# power_unit.net
KiCad netlist of a schematic drawn in Altium Designer
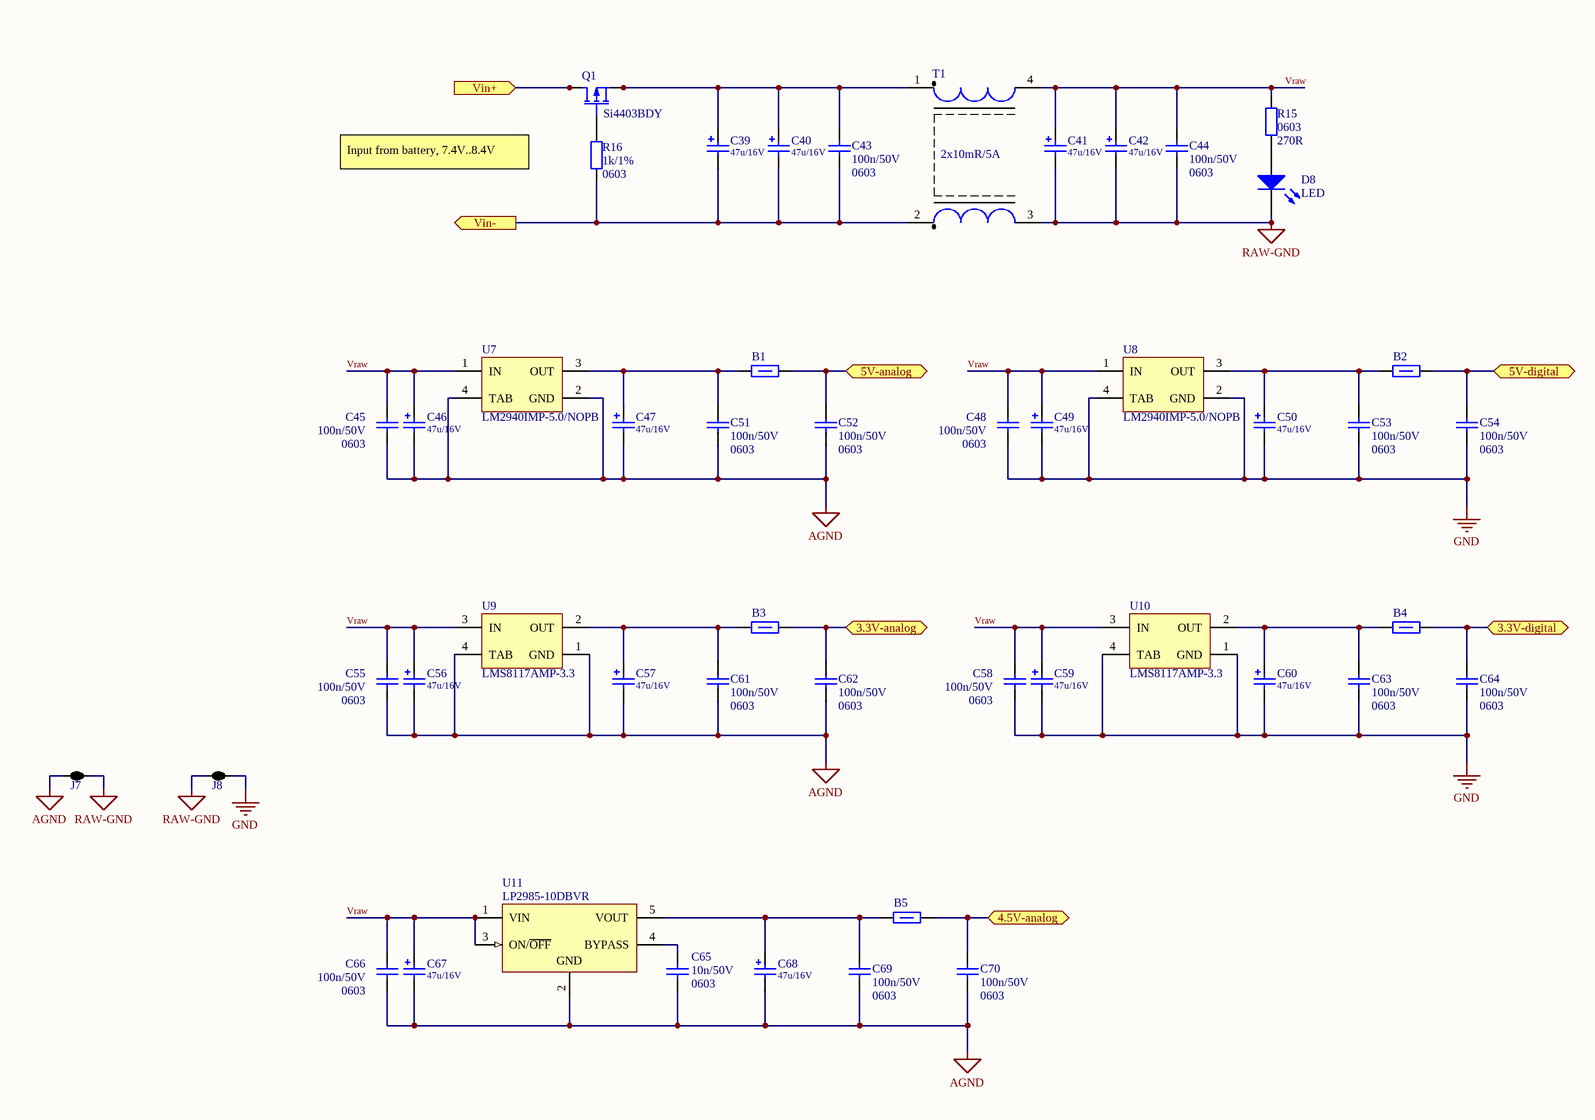
[diagram p0: power_unit.SchDoc]

(export (version "E")
  (design (tool "Eeschema 10.0.6"))
  (components
    (comp (ref "B1")
      (value "120R/100MHz")
      (footprint "SMD_FerriteBead_1206")
      (description "Ferrite bead, 1206, 0.02HM, 3.5A.")
      (fields (field (name "MANUFACTURER") "Murata") (field (name "MANUFACTURERPARTNUMBER") "BLM31PG121SH1L"))
      (libsource (lib "inductors") (part "BLM31PG121SH1L"))
    )
    (comp (ref "B2")
      (value "120R/100MHz")
      (footprint "SMD_FerriteBead_1206")
      (description "Ferrite bead, 1206, 0.02HM, 3.5A.")
      (fields (field (name "MANUFACTURER") "Murata") (field (name "MANUFACTURERPARTNUMBER") "BLM31PG121SH1L"))
      (libsource (lib "inductors") (part "BLM31PG121SH1L"))
    )
    (comp (ref "B3")
      (value "120R/100MHz")
      (footprint "SMD_FerriteBead_1206")
      (description "Ferrite bead, 1206, 0.02HM, 3.5A.")
      (fields (field (name "MANUFACTURER") "Murata") (field (name "MANUFACTURERPARTNUMBER") "BLM31PG121SH1L"))
      (libsource (lib "inductors") (part "BLM31PG121SH1L"))
    )
    (comp (ref "B4")
      (value "120R/100MHz")
      (footprint "SMD_FerriteBead_1206")
      (description "Ferrite bead, 1206, 0.02HM, 3.5A.")
      (fields (field (name "MANUFACTURER") "Murata") (field (name "MANUFACTURERPARTNUMBER") "BLM31PG121SH1L"))
      (libsource (lib "inductors") (part "BLM31PG121SH1L"))
    )
    (comp (ref "B5")
      (value "120R/100MHz")
      (footprint "SMD_FerriteBead_1206")
      (description "Ferrite bead, 1206, 0.02HM, 3.5A.")
      (fields (field (name "MANUFACTURER") "Murata") (field (name "MANUFACTURERPARTNUMBER") "BLM31PG121SH1L"))
      (libsource (lib "inductors") (part "BLM31PG121SH1L"))
    )
    (comp (ref "C39")
      (value "47u/16V")
      (footprint "Tantalum_cap_B")
      (description "Tantalum Capacitor")
      (libsource (lib "GG") (part "Cap Tantalum"))
    )
    (comp (ref "C40")
      (value "47u/16V")
      (footprint "Tantalum_cap_B")
      (description "Tantalum Capacitor")
      (libsource (lib "GG") (part "Cap Tantalum"))
    )
    (comp (ref "C41")
      (value "47u/16V")
      (footprint "Tantalum_cap_B")
      (description "Tantalum Capacitor")
      (libsource (lib "GG") (part "Cap Tantalum"))
    )
    (comp (ref "C42")
      (value "47u/16V")
      (footprint "Tantalum_cap_B")
      (description "Tantalum Capacitor")
      (libsource (lib "GG") (part "Cap Tantalum"))
    )
    (comp (ref "C43")
      (value "100n/50V")
      (footprint "SMD_Capacitor_0603")
      (description "Ceramic Cap Kemet COTS 100n/50V X7R 0603")
      (fields
        (field (name "MANUFACTURER") "Kemet")
        (field (name "MANUFACTURERPARTNUMBER") "C0603T104K5RALTU")
        (field (name "PACKAGE") "0603")
      )
      (libsource (lib "capacitors") (part "Cer_C0603T104K5RALTU"))
    )
    (comp (ref "C44")
      (value "100n/50V")
      (footprint "SMD_Capacitor_0603")
      (description "Ceramic Cap Kemet COTS 100n/50V X7R 0603")
      (fields
        (field (name "MANUFACTURER") "Kemet")
        (field (name "MANUFACTURERPARTNUMBER") "C0603T104K5RALTU")
        (field (name "PACKAGE") "0603")
      )
      (libsource (lib "capacitors") (part "Cer_C0603T104K5RALTU"))
    )
    (comp (ref "C45")
      (value "100n/50V")
      (footprint "SMD_Capacitor_0603")
      (description "Ceramic Cap Kemet COTS 100n/50V X7R 0603")
      (fields
        (field (name "MANUFACTURER") "Kemet")
        (field (name "MANUFACTURERPARTNUMBER") "C0603T104K5RALTU")
        (field (name "PACKAGE") "0603")
      )
      (libsource (lib "capacitors") (part "Cer_C0603T104K5RALTU"))
    )
    (comp (ref "C46")
      (value "47u/16V")
      (footprint "Tantalum_cap_B")
      (description "Tantalum Capacitor")
      (libsource (lib "GG") (part "Cap Tantalum"))
    )
    (comp (ref "C47")
      (value "47u/16V")
      (footprint "Tantalum_cap_B")
      (description "Tantalum Capacitor")
      (libsource (lib "GG") (part "Cap Tantalum"))
    )
    (comp (ref "C48")
      (value "100n/50V")
      (footprint "SMD_Capacitor_0603")
      (description "Ceramic Cap Kemet COTS 100n/50V X7R 0603")
      (fields
        (field (name "MANUFACTURER") "Kemet")
        (field (name "MANUFACTURERPARTNUMBER") "C0603T104K5RALTU")
        (field (name "PACKAGE") "0603")
      )
      (libsource (lib "capacitors") (part "Cer_C0603T104K5RALTU"))
    )
    (comp (ref "C49")
      (value "47u/16V")
      (footprint "Tantalum_cap_B")
      (description "Tantalum Capacitor")
      (libsource (lib "GG") (part "Cap Tantalum"))
    )
    (comp (ref "C50")
      (value "47u/16V")
      (footprint "Tantalum_cap_B")
      (description "Tantalum Capacitor")
      (libsource (lib "GG") (part "Cap Tantalum"))
    )
    (comp (ref "C51")
      (value "100n/50V")
      (footprint "SMD_Capacitor_0603")
      (description "Ceramic Cap Kemet COTS 100n/50V X7R 0603")
      (fields
        (field (name "MANUFACTURER") "Kemet")
        (field (name "MANUFACTURERPARTNUMBER") "C0603T104K5RALTU")
        (field (name "PACKAGE") "0603")
      )
      (libsource (lib "capacitors") (part "Cer_C0603T104K5RALTU"))
    )
    (comp (ref "C52")
      (value "100n/50V")
      (footprint "SMD_Capacitor_0603")
      (description "Ceramic Cap Kemet COTS 100n/50V X7R 0603")
      (fields
        (field (name "MANUFACTURER") "Kemet")
        (field (name "MANUFACTURERPARTNUMBER") "C0603T104K5RALTU")
        (field (name "PACKAGE") "0603")
      )
      (libsource (lib "capacitors") (part "Cer_C0603T104K5RALTU"))
    )
    (comp (ref "C53")
      (value "100n/50V")
      (footprint "SMD_Capacitor_0603")
      (description "Ceramic Cap Kemet COTS 100n/50V X7R 0603")
      (fields
        (field (name "MANUFACTURER") "Kemet")
        (field (name "MANUFACTURERPARTNUMBER") "C0603T104K5RALTU")
        (field (name "PACKAGE") "0603")
      )
      (libsource (lib "capacitors") (part "Cer_C0603T104K5RALTU"))
    )
    (comp (ref "C54")
      (value "100n/50V")
      (footprint "SMD_Capacitor_0603")
      (description "Ceramic Cap Kemet COTS 100n/50V X7R 0603")
      (fields
        (field (name "MANUFACTURER") "Kemet")
        (field (name "MANUFACTURERPARTNUMBER") "C0603T104K5RALTU")
        (field (name "PACKAGE") "0603")
      )
      (libsource (lib "capacitors") (part "Cer_C0603T104K5RALTU"))
    )
    (comp (ref "C55")
      (value "100n/50V")
      (footprint "SMD_Capacitor_0603")
      (description "Ceramic Cap Kemet COTS 100n/50V X7R 0603")
      (fields
        (field (name "MANUFACTURER") "Kemet")
        (field (name "MANUFACTURERPARTNUMBER") "C0603T104K5RALTU")
        (field (name "PACKAGE") "0603")
      )
      (libsource (lib "capacitors") (part "Cer_C0603T104K5RALTU"))
    )
    (comp (ref "C56")
      (value "47u/16V")
      (footprint "Tantalum_cap_B")
      (description "Tantalum Capacitor")
      (libsource (lib "GG") (part "Cap Tantalum"))
    )
    (comp (ref "C57")
      (value "47u/16V")
      (footprint "Tantalum_cap_B")
      (description "Tantalum Capacitor")
      (libsource (lib "GG") (part "Cap Tantalum"))
    )
    (comp (ref "C58")
      (value "100n/50V")
      (footprint "SMD_Capacitor_0603")
      (description "Ceramic Cap Kemet COTS 100n/50V X7R 0603")
      (fields
        (field (name "MANUFACTURER") "Kemet")
        (field (name "MANUFACTURERPARTNUMBER") "C0603T104K5RALTU")
        (field (name "PACKAGE") "0603")
      )
      (libsource (lib "capacitors") (part "Cer_C0603T104K5RALTU"))
    )
    (comp (ref "C59")
      (value "47u/16V")
      (footprint "Tantalum_cap_B")
      (description "Tantalum Capacitor")
      (libsource (lib "GG") (part "Cap Tantalum"))
    )
    (comp (ref "C60")
      (value "47u/16V")
      (footprint "Tantalum_cap_B")
      (description "Tantalum Capacitor")
      (libsource (lib "GG") (part "Cap Tantalum"))
    )
    (comp (ref "C61")
      (value "100n/50V")
      (footprint "SMD_Capacitor_0603")
      (description "Ceramic Cap Kemet COTS 100n/50V X7R 0603")
      (fields
        (field (name "MANUFACTURER") "Kemet")
        (field (name "MANUFACTURERPARTNUMBER") "C0603T104K5RALTU")
        (field (name "PACKAGE") "0603")
      )
      (libsource (lib "capacitors") (part "Cer_C0603T104K5RALTU"))
    )
    (comp (ref "C62")
      (value "100n/50V")
      (footprint "SMD_Capacitor_0603")
      (description "Ceramic Cap Kemet COTS 100n/50V X7R 0603")
      (fields
        (field (name "MANUFACTURER") "Kemet")
        (field (name "MANUFACTURERPARTNUMBER") "C0603T104K5RALTU")
        (field (name "PACKAGE") "0603")
      )
      (libsource (lib "capacitors") (part "Cer_C0603T104K5RALTU"))
    )
    (comp (ref "C63")
      (value "100n/50V")
      (footprint "SMD_Capacitor_0603")
      (description "Ceramic Cap Kemet COTS 100n/50V X7R 0603")
      (fields
        (field (name "MANUFACTURER") "Kemet")
        (field (name "MANUFACTURERPARTNUMBER") "C0603T104K5RALTU")
        (field (name "PACKAGE") "0603")
      )
      (libsource (lib "capacitors") (part "Cer_C0603T104K5RALTU"))
    )
    (comp (ref "C64")
      (value "100n/50V")
      (footprint "SMD_Capacitor_0603")
      (description "Ceramic Cap Kemet COTS 100n/50V X7R 0603")
      (fields
        (field (name "MANUFACTURER") "Kemet")
        (field (name "MANUFACTURERPARTNUMBER") "C0603T104K5RALTU")
        (field (name "PACKAGE") "0603")
      )
      (libsource (lib "capacitors") (part "Cer_C0603T104K5RALTU"))
    )
    (comp (ref "C65")
      (value "10n/50V")
      (footprint "SMD_Capacitor_0603")
      (description "Cap")
      (fields (field (name "PACKAGE") "0603"))
      (libsource (lib "capacitors") (part "Cap"))
    )
    (comp (ref "C66")
      (value "100n/50V")
      (footprint "SMD_Capacitor_0603")
      (description "Ceramic Cap Kemet COTS 100n/50V X7R 0603")
      (fields
        (field (name "MANUFACTURER") "Kemet")
        (field (name "MANUFACTURERPARTNUMBER") "C0603T104K5RALTU")
        (field (name "PACKAGE") "0603")
      )
      (libsource (lib "capacitors") (part "Cer_C0603T104K5RALTU"))
    )
    (comp (ref "C67")
      (value "47u/16V")
      (footprint "Tantalum_cap_B")
      (description "Tantalum Capacitor")
      (libsource (lib "GG") (part "Cap Tantalum"))
    )
    (comp (ref "C68")
      (value "47u/16V")
      (footprint "Tantalum_cap_B")
      (description "Tantalum Capacitor")
      (libsource (lib "GG") (part "Cap Tantalum"))
    )
    (comp (ref "C69")
      (value "100n/50V")
      (footprint "SMD_Capacitor_0603")
      (description "Ceramic Cap Kemet COTS 100n/50V X7R 0603")
      (fields
        (field (name "MANUFACTURER") "Kemet")
        (field (name "MANUFACTURERPARTNUMBER") "C0603T104K5RALTU")
        (field (name "PACKAGE") "0603")
      )
      (libsource (lib "capacitors") (part "Cer_C0603T104K5RALTU"))
    )
    (comp (ref "C70")
      (value "100n/50V")
      (footprint "SMD_Capacitor_0603")
      (description "Ceramic Cap Kemet COTS 100n/50V X7R 0603")
      (fields
        (field (name "MANUFACTURER") "Kemet")
        (field (name "MANUFACTURERPARTNUMBER") "C0603T104K5RALTU")
        (field (name "PACKAGE") "0603")
      )
      (libsource (lib "capacitors") (part "Cer_C0603T104K5RALTU"))
    )
    (comp (ref "D8")
      (value "LED")
      (footprint "LED 0805 RED")
      (description "Typical BLUE SiC LED")
      (fields (field (name "PUBLISHER") "Altium Limited"))
      (libsource (lib "Miscellaneous Devices") (part "LED3"))
    )
    (comp (ref "J7")
      (value "2 way net tie junction")
      (footprint "2way_MP")
      (libsource (lib "NetTieLib") (part "2way"))
    )
    (comp (ref "J8")
      (value "2 way net tie junction")
      (footprint "2way_MP")
      (libsource (lib "NetTieLib") (part "2way"))
    )
    (comp (ref "Q1")
      (value "Si4403BDY")
      (footprint "SOIC-8_M")
      (description "P-Channel 1.8 V (G-S) MOSFET")
      (libsource (lib "GG") (part "Si4403BDY"))
    )
    (comp (ref "R15")
      (value "0603")
      (footprint "SMD_Resistor_0603")
      (description "Resistor")
      (fields (field (name "ALTIUM_VALUE") "270R") (field (name "PUBLISHER") "Altium Limited"))
      (libsource (lib "Miscellaneous Devices") (part "Res2"))
    )
    (comp (ref "R16")
      (value "1k/1%")
      (footprint "SMD_Resistor_0603")
      (description "1k/1% Vishay CRCW 0603 Resistor. 100mW, 100ppm, 75V.")
      (fields
        (field (name "MANUFACTURER") "Vishay")
        (field (name "MANUFACTURERPARTNUMBER") "CRCW06031K00FKxxxx")
        (field (name "PACKAGE") "0603")
      )
      (libsource (lib "resistors") (part "CRCW06031K00FKxxxx"))
    )
    (comp (ref "T1")
      (value "2x10mR/5A")
      (footprint "TDK_ACM7060")
      (description "TDK ACM7060-301 Common Mode Choke")
      (fields
        (field (name "MANUFACTURER") "TDK")
        (field (name "MANUFACTURERPARTNUMBER") "ACM7060-301-2PL-TL01")
      )
      (libsource (lib "GG") (part "ACM7060-301-2PL-TL01"))
    )
    (comp (ref "U7")
      (value "LM2940IMP-5.0/NOPB")
      (footprint "MP04A_N")
      (description "1A Low Dropout Regulator, 4-pin SOT-223, Pb-Free")
      (fields (field (name "MANUFACTURER") "National Semiconductor"))
      (libsource (lib "National Semiconductor LDO") (part "LM2940IMP-5.0/NOPB"))
    )
    (comp (ref "U8")
      (value "LM2940IMP-5.0/NOPB")
      (footprint "MP04A_N")
      (description "1A Low Dropout Regulator, 4-pin SOT-223, Pb-Free")
      (fields (field (name "MANUFACTURER") "National Semiconductor"))
      (libsource (lib "National Semiconductor LDO") (part "LM2940IMP-5.0/NOPB"))
    )
    (comp (ref "U9")
      (value "LMS8117AMP-3.3")
      (footprint "MP04A_M")
      (description "1A Low-Dropout Linear Regulator, 4-pin SOT-223")
      (fields (field (name "MANUFACTURER") "National Semiconductor"))
      (libsource (lib "National Semiconductor LDO") (part "LMS8117AMP-3.3"))
    )
    (comp (ref "U10")
      (value "LMS8117AMP-3.3")
      (footprint "MP04A_M")
      (description "1A Low-Dropout Linear Regulator, 4-pin SOT-223")
      (fields (field (name "MANUFACTURER") "National Semiconductor"))
      (libsource (lib "National Semiconductor LDO") (part "LMS8117AMP-3.3"))
    )
    (comp (ref "U11")
      (value "LP2985-10DBVR")
      (footprint "TI-DBV5_N")
      (fields (field (name "MANUFACTURER") "Texas Instruments"))
      (libsource (lib "TI Power Management Linear Regulator Single Channel LDO (0-350mA)") (part "LP2985-10DBVR"))
    )
  )
  (nets
    (net (code "1") (name "/3.3V-analog") (class "Default")
      (node (ref "B3") (pin "2") (pinfunction "2_2") (pintype "passive"))
      (node (ref "C62") (pin "1") (pinfunction "1_1") (pintype "passive"))
    )
    (net (code "2") (name "/3.3V-digital") (class "Default")
      (node (ref "B4") (pin "2") (pinfunction "2_2") (pintype "passive"))
      (node (ref "C64") (pin "1") (pinfunction "1_1") (pintype "passive"))
    )
    (net (code "3") (name "/4.5V-analog") (class "Default")
      (node (ref "B5") (pin "2") (pinfunction "2_2") (pintype "passive"))
      (node (ref "C70") (pin "1") (pinfunction "1_1") (pintype "passive"))
    )
    (net (code "4") (name "/5V-analog") (class "Default")
      (node (ref "B1") (pin "2") (pinfunction "2_2") (pintype "passive"))
      (node (ref "C52") (pin "1") (pinfunction "1_1") (pintype "passive"))
    )
    (net (code "5") (name "/5V-digital") (class "Default")
      (node (ref "B2") (pin "2") (pinfunction "2_2") (pintype "passive"))
      (node (ref "C54") (pin "1") (pinfunction "1_1") (pintype "passive"))
    )
    (net (code "6") (name "/Vin+") (class "Default")
      (node (ref "Q1") (pin "5") (pinfunction "D_5") (pintype "passive"))
      (node (ref "Q1") (pin "6") (pinfunction "D_6") (pintype "passive"))
      (node (ref "Q1") (pin "7") (pinfunction "D_7") (pintype "passive"))
      (node (ref "Q1") (pin "8") (pinfunction "D_8") (pintype "passive"))
    )
    (net (code "7") (name "/Vin-") (class "Default")
      (node (ref "C39") (pin "2") (pinfunction "2_2") (pintype "passive"))
      (node (ref "C40") (pin "2") (pinfunction "2_2") (pintype "passive"))
      (node (ref "C43") (pin "2") (pinfunction "2_2") (pintype "passive"))
      (node (ref "R16") (pin "2") (pinfunction "2_2") (pintype "passive"))
      (node (ref "T1") (pin "2") (pinfunction "2_2") (pintype "passive"))
    )
    (net (code "8") (name "/Vraw") (class "Default")
      (node (ref "C41") (pin "1") (pinfunction "1_1") (pintype "passive"))
      (node (ref "C42") (pin "1") (pinfunction "1_1") (pintype "passive"))
      (node (ref "C44") (pin "1") (pinfunction "1_1") (pintype "passive"))
      (node (ref "C45") (pin "1") (pinfunction "1_1") (pintype "passive"))
      (node (ref "C46") (pin "1") (pinfunction "1_1") (pintype "passive"))
      (node (ref "C48") (pin "1") (pinfunction "1_1") (pintype "passive"))
      (node (ref "C49") (pin "1") (pinfunction "1_1") (pintype "passive"))
      (node (ref "C55") (pin "1") (pinfunction "1_1") (pintype "passive"))
      (node (ref "C56") (pin "1") (pinfunction "1_1") (pintype "passive"))
      (node (ref "C58") (pin "1") (pinfunction "1_1") (pintype "passive"))
      (node (ref "C59") (pin "1") (pinfunction "1_1") (pintype "passive"))
      (node (ref "C66") (pin "1") (pinfunction "1_1") (pintype "passive"))
      (node (ref "C67") (pin "1") (pinfunction "1_1") (pintype "passive"))
      (node (ref "R15") (pin "1") (pinfunction "1_1") (pintype "passive"))
      (node (ref "T1") (pin "4") (pinfunction "4_4") (pintype "passive"))
      (node (ref "U10") (pin "3") (pinfunction "IN_3") (pintype "power_in"))
      (node (ref "U11") (pin "1") (pinfunction "VIN_1") (pintype "power_in"))
      (node (ref "U11") (pin "3") (pinfunction "ON/~{OFF}_3") (pintype "input"))
      (node (ref "U7") (pin "1") (pinfunction "IN_1") (pintype "power_in"))
      (node (ref "U8") (pin "1") (pinfunction "IN_1") (pintype "power_in"))
      (node (ref "U9") (pin "3") (pinfunction "IN_3") (pintype "power_in"))
    )
    (net (code "9") (name "AGND") (class "Default")
      (node (ref "C45") (pin "2") (pinfunction "2_2") (pintype "passive"))
      (node (ref "C46") (pin "2") (pinfunction "2_2") (pintype "passive"))
      (node (ref "C47") (pin "2") (pinfunction "2_2") (pintype "passive"))
      (node (ref "C51") (pin "2") (pinfunction "2_2") (pintype "passive"))
      (node (ref "C52") (pin "2") (pinfunction "2_2") (pintype "passive"))
      (node (ref "C55") (pin "2") (pinfunction "2_2") (pintype "passive"))
      (node (ref "C56") (pin "2") (pinfunction "2_2") (pintype "passive"))
      (node (ref "C57") (pin "2") (pinfunction "2_2") (pintype "passive"))
      (node (ref "C61") (pin "2") (pinfunction "2_2") (pintype "passive"))
      (node (ref "C62") (pin "2") (pinfunction "2_2") (pintype "passive"))
      (node (ref "C65") (pin "2") (pinfunction "2_2") (pintype "passive"))
      (node (ref "C66") (pin "2") (pinfunction "2_2") (pintype "passive"))
      (node (ref "C67") (pin "2") (pinfunction "2_2") (pintype "passive"))
      (node (ref "C68") (pin "2") (pinfunction "2_2") (pintype "passive"))
      (node (ref "C69") (pin "2") (pinfunction "2_2") (pintype "passive"))
      (node (ref "C70") (pin "2") (pinfunction "2_2") (pintype "passive"))
      (node (ref "J7") (pin "2") (pinfunction "2_2") (pintype "passive"))
      (node (ref "U11") (pin "2") (pinfunction "GND_2") (pintype "power_in"))
      (node (ref "U7") (pin "2") (pinfunction "GND_2") (pintype "power_in"))
      (node (ref "U7") (pin "4") (pinfunction "TAB_4") (pintype "power_in"))
      (node (ref "U9") (pin "1") (pinfunction "GND_1") (pintype "power_in"))
      (node (ref "U9") (pin "4") (pinfunction "TAB_4") (pintype "power_in"))
    )
    (net (code "10") (name "GND") (class "Default")
      (node (ref "C48") (pin "2") (pinfunction "2_2") (pintype "passive"))
      (node (ref "C49") (pin "2") (pinfunction "2_2") (pintype "passive"))
      (node (ref "C50") (pin "2") (pinfunction "2_2") (pintype "passive"))
      (node (ref "C53") (pin "2") (pinfunction "2_2") (pintype "passive"))
      (node (ref "C54") (pin "2") (pinfunction "2_2") (pintype "passive"))
      (node (ref "C58") (pin "2") (pinfunction "2_2") (pintype "passive"))
      (node (ref "C59") (pin "2") (pinfunction "2_2") (pintype "passive"))
      (node (ref "C60") (pin "2") (pinfunction "2_2") (pintype "passive"))
      (node (ref "C63") (pin "2") (pinfunction "2_2") (pintype "passive"))
      (node (ref "C64") (pin "2") (pinfunction "2_2") (pintype "passive"))
      (node (ref "J8") (pin "1") (pinfunction "1_1") (pintype "passive"))
      (node (ref "U10") (pin "1") (pinfunction "GND_1") (pintype "power_in"))
      (node (ref "U10") (pin "4") (pinfunction "TAB_4") (pintype "power_in"))
      (node (ref "U8") (pin "2") (pinfunction "GND_2") (pintype "power_in"))
      (node (ref "U8") (pin "4") (pinfunction "TAB_4") (pintype "power_in"))
    )
    (net (code "11") (name "Net-(C39-Pad1)") (class "Default")
      (node (ref "C39") (pin "1") (pinfunction "1_1") (pintype "passive"))
      (node (ref "C40") (pin "1") (pinfunction "1_1") (pintype "passive"))
      (node (ref "C43") (pin "1") (pinfunction "1_1") (pintype "passive"))
      (node (ref "Q1") (pin "1") (pinfunction "S_1") (pintype "passive"))
      (node (ref "Q1") (pin "2") (pinfunction "S_2") (pintype "passive"))
      (node (ref "Q1") (pin "3") (pinfunction "S_3") (pintype "passive"))
      (node (ref "T1") (pin "1") (pinfunction "1_1") (pintype "passive"))
    )
    (net (code "12") (name "Net-(D8-A)") (class "Default")
      (node (ref "D8") (pin "1") (pinfunction "A_1") (pintype "passive"))
      (node (ref "R15") (pin "2") (pinfunction "2_2") (pintype "passive"))
    )
    (net (code "13") (name "Net-(Q1-G)") (class "Default")
      (node (ref "Q1") (pin "4") (pinfunction "G_4") (pintype "passive"))
      (node (ref "R16") (pin "1") (pinfunction "1_1") (pintype "passive"))
    )
    (net (code "14") (name "Net-(U7-OUT)") (class "Default")
      (node (ref "B1") (pin "1") (pinfunction "1_1") (pintype "passive"))
      (node (ref "C47") (pin "1") (pinfunction "1_1") (pintype "passive"))
      (node (ref "C51") (pin "1") (pinfunction "1_1") (pintype "passive"))
      (node (ref "U7") (pin "3") (pinfunction "OUT_3") (pintype "power_in"))
    )
    (net (code "15") (name "Net-(U8-OUT)") (class "Default")
      (node (ref "B2") (pin "1") (pinfunction "1_1") (pintype "passive"))
      (node (ref "C50") (pin "1") (pinfunction "1_1") (pintype "passive"))
      (node (ref "C53") (pin "1") (pinfunction "1_1") (pintype "passive"))
      (node (ref "U8") (pin "3") (pinfunction "OUT_3") (pintype "power_in"))
    )
    (net (code "16") (name "Net-(U9-OUT)") (class "Default")
      (node (ref "B3") (pin "1") (pinfunction "1_1") (pintype "passive"))
      (node (ref "C57") (pin "1") (pinfunction "1_1") (pintype "passive"))
      (node (ref "C61") (pin "1") (pinfunction "1_1") (pintype "passive"))
      (node (ref "U9") (pin "2") (pinfunction "OUT_2") (pintype "power_in"))
    )
    (net (code "17") (name "Net-(U10-OUT)") (class "Default")
      (node (ref "B4") (pin "1") (pinfunction "1_1") (pintype "passive"))
      (node (ref "C60") (pin "1") (pinfunction "1_1") (pintype "passive"))
      (node (ref "C63") (pin "1") (pinfunction "1_1") (pintype "passive"))
      (node (ref "U10") (pin "2") (pinfunction "OUT_2") (pintype "power_in"))
    )
    (net (code "18") (name "Net-(U11-BYPASS)") (class "Default")
      (node (ref "C65") (pin "1") (pinfunction "1_1") (pintype "passive"))
      (node (ref "U11") (pin "4") (pinfunction "BYPASS_4") (pintype "passive"))
    )
    (net (code "19") (name "Net-(U11-VOUT)") (class "Default")
      (node (ref "B5") (pin "1") (pinfunction "1_1") (pintype "passive"))
      (node (ref "C68") (pin "1") (pinfunction "1_1") (pintype "passive"))
      (node (ref "C69") (pin "1") (pinfunction "1_1") (pintype "passive"))
      (node (ref "U11") (pin "5") (pinfunction "VOUT_5") (pintype "power_in"))
    )
    (net (code "20") (name "RAW-GND") (class "Default")
      (node (ref "C41") (pin "2") (pinfunction "2_2") (pintype "passive"))
      (node (ref "C42") (pin "2") (pinfunction "2_2") (pintype "passive"))
      (node (ref "C44") (pin "2") (pinfunction "2_2") (pintype "passive"))
      (node (ref "D8") (pin "2") (pinfunction "K_2") (pintype "passive"))
      (node (ref "J7") (pin "1") (pinfunction "1_1") (pintype "passive"))
      (node (ref "J8") (pin "2") (pinfunction "2_2") (pintype "passive"))
      (node (ref "T1") (pin "3") (pinfunction "3_3") (pintype "passive"))
    )
  )
)
